# power_dist.net
KiCad netlist of a schematic drawn in EAGLE
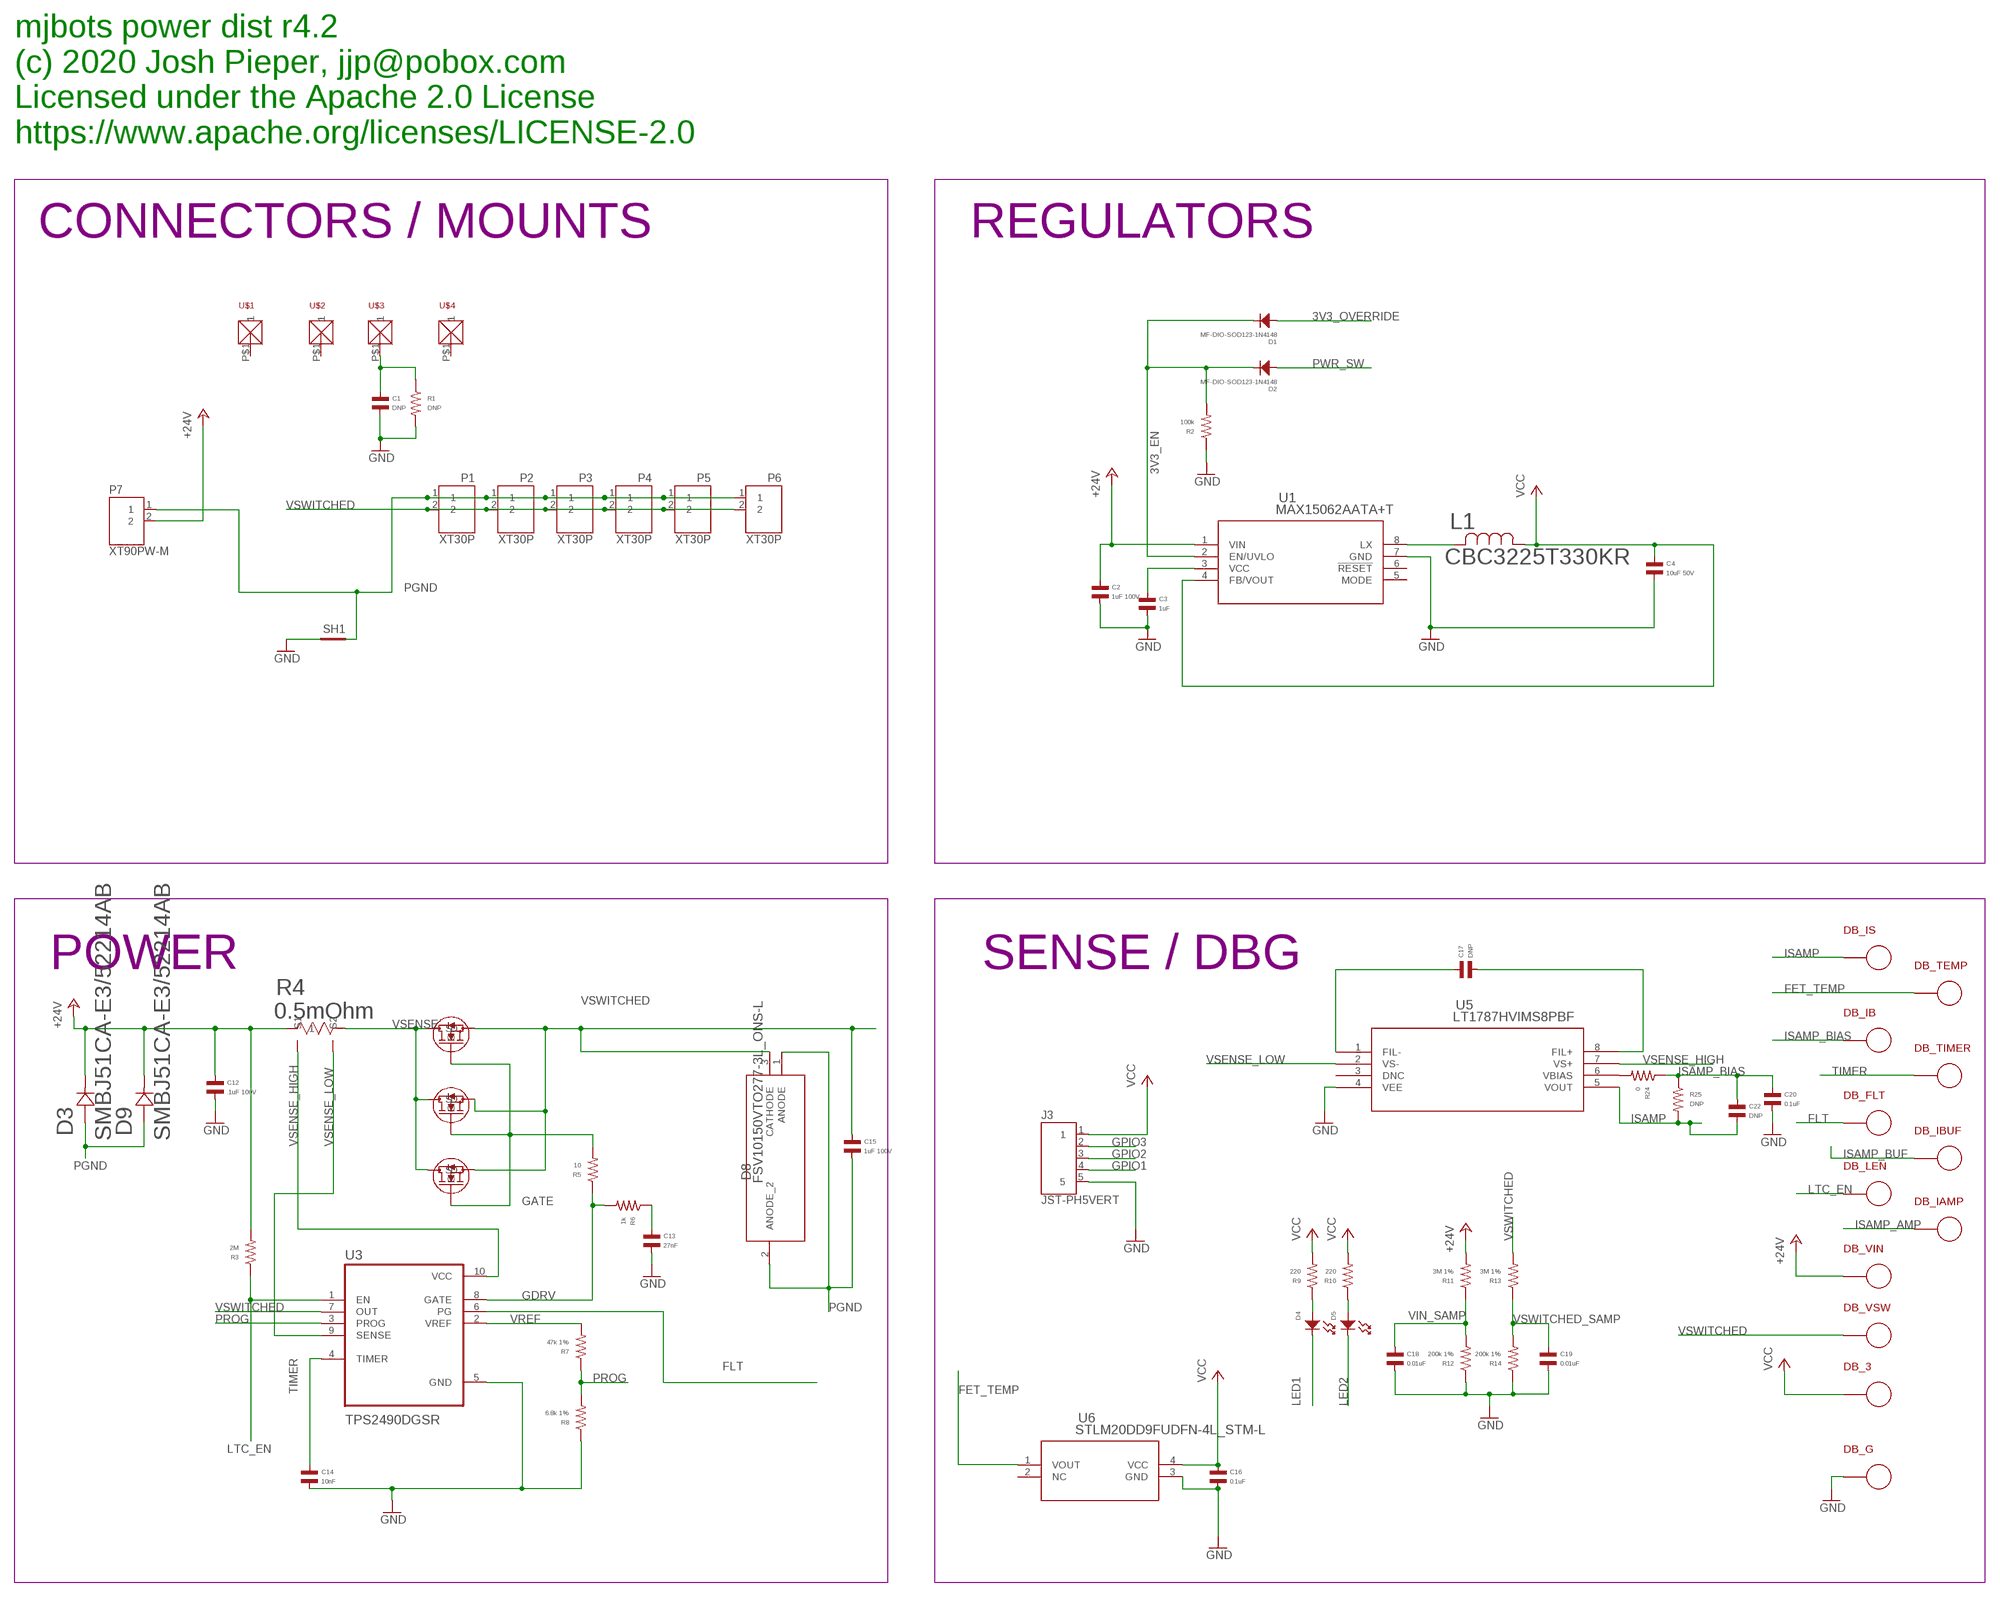
[diagram p0: schematic, sheet 1, part 1 of 2]
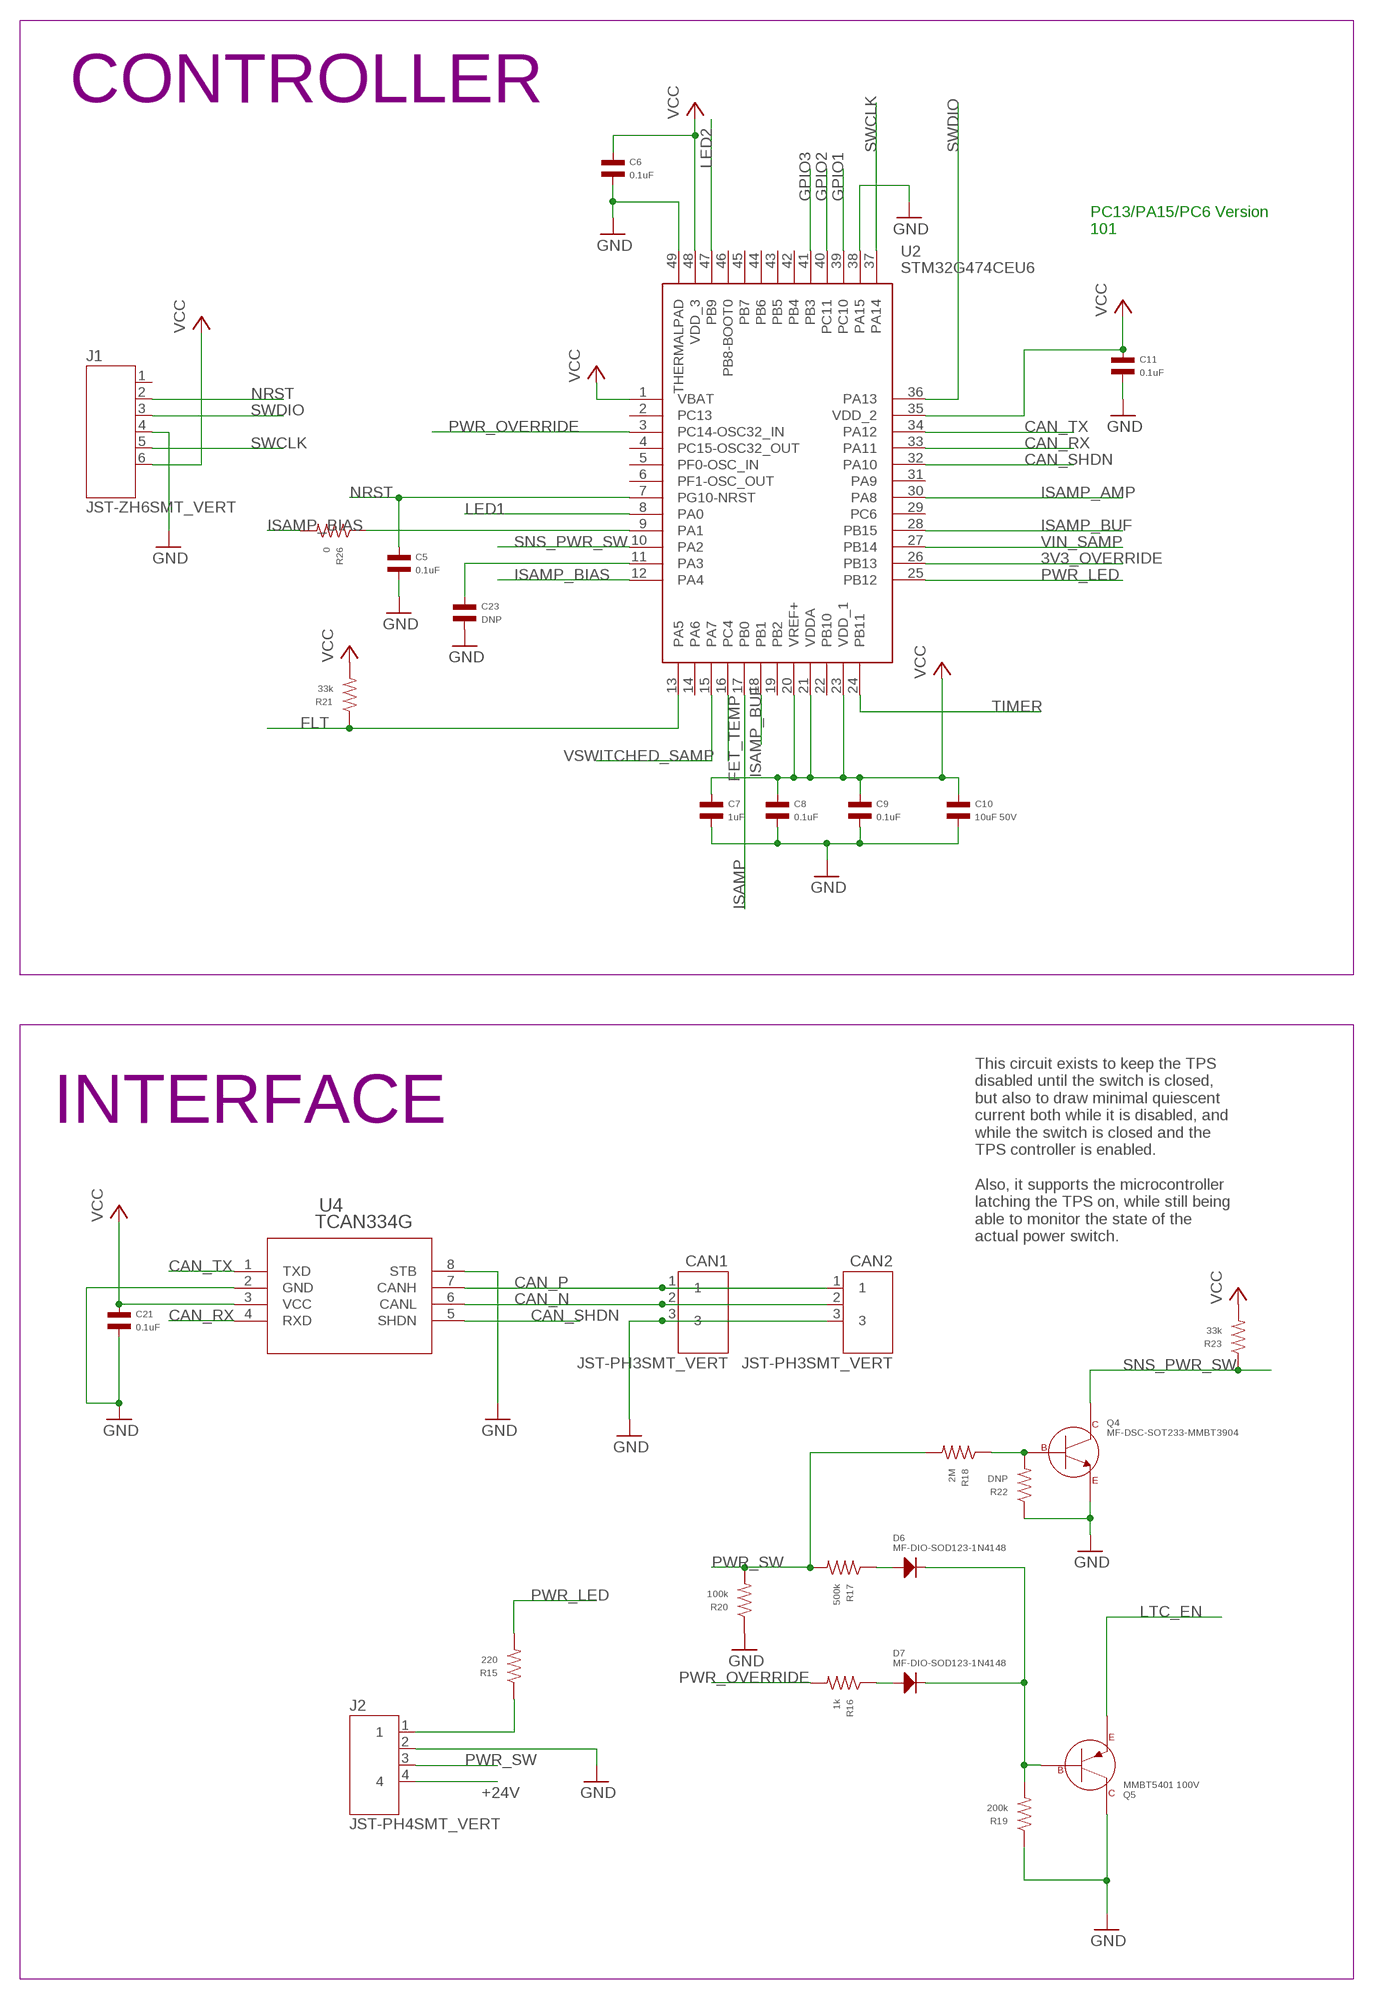
[diagram p1: schematic, sheet 1, part 2 of 2]

(export (version "E")
  (design (tool "Eeschema 10.0.6"))
  (components
    (comp (ref "C1")
      (value "DNP")
      (footprint "eagle-import:C0603")
      (fields (field (name "POPULATE") "0"))
      (libsource (lib "eagle-import") (part "CAPACITOR_NP_0603"))
    )
    (comp (ref "C2")
      (value "1uF 100V")
      (footprint "eagle-import:C0805")
      (fields (field (name "MF") "MURATA") (field (name "MPN") "GCM21BC72A105KE36L"))
      (libsource (lib "eagle-import") (part "CAPACITOR_NP_0805"))
    )
    (comp (ref "C3")
      (value "1uF")
      (footprint "eagle-import:C0603")
      (fields (field (name "HOUSEPART") "1") (field (name "MPN") "MF-CAP-0603-1uF"))
      (libsource (lib "eagle-import") (part "CAPACITOR_NP_0603"))
    )
    (comp (ref "C4")
      (value "10uF 50V")
      (footprint "eagle-import:C1206")
      (fields (field (name "MF") "TDK") (field (name "MPN") "C3216X7R1H106K160AE"))
      (libsource (lib "eagle-import") (part "CAPACITOR_NP_1206"))
    )
    (comp (ref "C5")
      (value "0.1uF")
      (footprint "eagle-import:C0603")
      (fields (field (name "HOUSEPART") "1") (field (name "MPN") "MF-CAP-0603-0.1uF"))
      (libsource (lib "eagle-import") (part "CAPACITOR_NP_0603"))
    )
    (comp (ref "C6")
      (value "0.1uF")
      (footprint "eagle-import:C0603")
      (fields (field (name "HOUSEPART") "1") (field (name "MPN") "MF-CAP-0603-0.1uF"))
      (libsource (lib "eagle-import") (part "CAPACITOR_NP_0603"))
    )
    (comp (ref "C7")
      (value "1uF")
      (footprint "eagle-import:C0603")
      (fields (field (name "HOUSEPART") "1") (field (name "MPN") "MF-CAP-0603-1uF"))
      (libsource (lib "eagle-import") (part "CAPACITOR_NP_0603"))
    )
    (comp (ref "C8")
      (value "0.1uF")
      (footprint "eagle-import:C0603")
      (fields (field (name "HOUSEPART") "1") (field (name "MPN") "MF-CAP-0603-0.1uF"))
      (libsource (lib "eagle-import") (part "CAPACITOR_NP_0603"))
    )
    (comp (ref "C9")
      (value "0.1uF")
      (footprint "eagle-import:C0603")
      (fields (field (name "HOUSEPART") "1") (field (name "MPN") "MF-CAP-0603-0.1uF"))
      (libsource (lib "eagle-import") (part "CAPACITOR_NP_0603"))
    )
    (comp (ref "C10")
      (value "10uF 50V")
      (footprint "eagle-import:C1206")
      (fields (field (name "MF") "TDK") (field (name "MPN") "C3216X7R1H106K160AE"))
      (libsource (lib "eagle-import") (part "CAPACITOR_NP_1206"))
    )
    (comp (ref "C11")
      (value "0.1uF")
      (footprint "eagle-import:C0603")
      (fields (field (name "HOUSEPART") "1") (field (name "MPN") "MF-CAP-0603-0.1uF"))
      (libsource (lib "eagle-import") (part "CAPACITOR_NP_0603"))
    )
    (comp (ref "C12")
      (value ".1uF 100V")
      (footprint "eagle-import:C0603")
      (fields (field (name "HOUSEPART") "1") (field (name "MPN") "MF-CAP-0603-0.1uF"))
      (libsource (lib "eagle-import") (part "CAPACITOR_NP_0603"))
    )
    (comp (ref "C13")
      (value "27nF")
      (footprint "eagle-import:C0603")
      (fields (field (name "HOUSEPART") "1"))
      (libsource (lib "eagle-import") (part "CAPACITOR_NP_0603"))
    )
    (comp (ref "C14")
      (value "10nF")
      (footprint "eagle-import:C0603")
      (fields (field (name "HOUSEPART") "1") (field (name "MPN") "MF-CAP-0603-0.1uF"))
      (libsource (lib "eagle-import") (part "CAPACITOR_NP_0603"))
    )
    (comp (ref "C15")
      (value "1uF 100V")
      (footprint "eagle-import:C0805")
      (fields (field (name "MF") "MURATA") (field (name "MPN") "GCM21BC72A105KE36L"))
      (libsource (lib "eagle-import") (part "CAPACITOR_NP_0805"))
    )
    (comp (ref "C16")
      (value "0.1uF")
      (footprint "eagle-import:C0603")
      (fields (field (name "HOUSEPART") "1") (field (name "MPN") "MF-CAP-0603-0.1uF"))
      (libsource (lib "eagle-import") (part "CAPACITOR_NP_0603"))
    )
    (comp (ref "C17")
      (value "DNP")
      (footprint "eagle-import:C0603")
      (fields (field (name "POPULATE") "0"))
      (libsource (lib "eagle-import") (part "CAPACITOR_NP_0603"))
    )
    (comp (ref "C18")
      (value "0.01uF")
      (footprint "eagle-import:C0603")
      (fields (field (name "HOUSEPART") "1") (field (name "MPN") "MF-CAP-0603-0.01uF"))
      (libsource (lib "eagle-import") (part "CAPACITOR_NP_0603"))
    )
    (comp (ref "C19")
      (value "0.01uF")
      (footprint "eagle-import:C0603")
      (fields (field (name "HOUSEPART") "1") (field (name "MPN") "MF-CAP-0603-0.01uF"))
      (libsource (lib "eagle-import") (part "CAPACITOR_NP_0603"))
    )
    (comp (ref "C20")
      (value "0.1uF")
      (footprint "eagle-import:C0603")
      (fields (field (name "HOUSEPART") "1") (field (name "MPN") "MF-CAP-0603-0.1uF"))
      (libsource (lib "eagle-import") (part "CAPACITOR_NP_0603"))
    )
    (comp (ref "C21")
      (value "0.1uF")
      (footprint "eagle-import:C0603")
      (fields (field (name "HOUSEPART") "1") (field (name "MPN") "MF-CAP-0603-0.1uF"))
      (libsource (lib "eagle-import") (part "CAPACITOR_NP_0603"))
    )
    (comp (ref "C22")
      (value "DNP")
      (footprint "eagle-import:C0603")
      (fields (field (name "HOUSEPART") "1") (field (name "POPULATE") "0"))
      (libsource (lib "eagle-import") (part "CAPACITOR_NP_0603"))
    )
    (comp (ref "C23")
      (value "DNP")
      (footprint "eagle-import:C0603")
      (fields (field (name "HOUSEPART") "1") (field (name "POPULATE") "0"))
      (libsource (lib "eagle-import") (part "CAPACITOR_NP_0603"))
    )
    (comp (ref "CAN1")
      (value "JST-PH3SMT_VERT")
      (footprint "eagle-import:JST_B3B_PH-SM4-TB(LF)(SN)")
      (fields (field (name "MF") "JST") (field (name "MPN") "B3B-PH-SM4-TB(LF)(SN)"))
      (libsource (lib "eagle-import") (part "JST-PH3SMT_VERT"))
    )
    (comp (ref "CAN2")
      (value "JST-PH3SMT_VERT")
      (footprint "eagle-import:JST_B3B_PH-SM4-TB(LF)(SN)")
      (fields (field (name "MF") "JST") (field (name "MPN") "B3B-PH-SM4-TB(LF)(SN)"))
      (libsource (lib "eagle-import") (part "JST-PH3SMT_VERT"))
    )
    (comp (ref "D1")
      (value "MF-DIO-SOD123-1N4148")
      (footprint "eagle-import:SOD-123")
      (fields (field (name "HOUSEPART") "YES"))
      (libsource (lib "eagle-import") (part "DIODES_SOD-123_1N4148"))
    )
    (comp (ref "D2")
      (value "MF-DIO-SOD123-1N4148")
      (footprint "eagle-import:SOD-123")
      (fields (field (name "HOUSEPART") "YES"))
      (libsource (lib "eagle-import") (part "DIODES_SOD-123_1N4148"))
    )
    (comp (ref "D3")
      (value "SMBJ51CA-E3/52214AB")
      (footprint "eagle-import:DIODE_DO-214AB")
      (fields (field (name "MPN") "SMC5K51A-M3/I"))
      (libsource (lib "eagle-import") (part "SMBJ51CA-E3/52214AB"))
    )
    (comp (ref "D4")
      (value "LED_SINGLE-0603")
      (footprint "eagle-import:LED0603")
      (fields
        (field (name "HOUSEPART") "NO")
        (field (name "HOUSEPART_1") "1")
        (field (name "MPN") "MF-LED-0603-RED")
      )
      (libsource (lib "eagle-import") (part "LED_SINGLE-0603"))
    )
    (comp (ref "D5")
      (value "LED_SINGLE-0603")
      (footprint "eagle-import:LED0603")
      (fields
        (field (name "HOUSEPART") "NO")
        (field (name "HOUSEPART_1") "1")
        (field (name "MPN") "MF-LED-0603-RED")
      )
      (libsource (lib "eagle-import") (part "LED_SINGLE-0603"))
    )
    (comp (ref "D6")
      (value "MF-DIO-SOD123-1N4148")
      (footprint "eagle-import:SOD-123")
      (fields (field (name "HOUSEPART") "YES"))
      (libsource (lib "eagle-import") (part "DIODES_SOD-123_1N4148"))
    )
    (comp (ref "D7")
      (value "MF-DIO-SOD123-1N4148")
      (footprint "eagle-import:SOD-123")
      (fields (field (name "HOUSEPART") "YES"))
      (libsource (lib "eagle-import") (part "DIODES_SOD-123_1N4148"))
    )
    (comp (ref "D8")
      (value "FSV10150VTO277-3L_ONS-L")
      (footprint "eagle-import:TO277-3L_ONS-L")
      (fields
        (field (name "MANUFACTURER_PART_NUMBER") "FSV10150V")
        (field (name "COPYRIGHT") "Copyright (C) 2018 Accelerated Designs. All rights reserved")
      )
      (libsource (lib "eagle-import") (part "FSV10150VTO277-3L_ONS-L"))
    )
    (comp (ref "D9")
      (value "SMBJ51CA-E3/52214AB")
      (footprint "eagle-import:DIODE_DO-214AB")
      (fields (field (name "MPN") "SMC5K51A-M3/I"))
      (libsource (lib "eagle-import") (part "SMBJ51CA-E3/52214AB"))
    )
    (comp (ref "DB_3")
      (value "PAD24AWG_PAD")
      (footprint "eagle-import:24AWG_PAD")
      (libsource (lib "eagle-import") (part "PAD24AWG_PAD"))
    )
    (comp (ref "DB_FLT")
      (value "PAD24AWG_PAD")
      (footprint "eagle-import:24AWG_PAD")
      (libsource (lib "eagle-import") (part "PAD24AWG_PAD"))
    )
    (comp (ref "DB_G")
      (value "PAD24AWG_PAD")
      (footprint "eagle-import:24AWG_PAD")
      (libsource (lib "eagle-import") (part "PAD24AWG_PAD"))
    )
    (comp (ref "DB_IAMP")
      (value "PAD24AWG_PAD")
      (footprint "eagle-import:24AWG_PAD")
      (libsource (lib "eagle-import") (part "PAD24AWG_PAD"))
    )
    (comp (ref "DB_IB")
      (value "PAD24AWG_PAD")
      (footprint "eagle-import:24AWG_PAD")
      (libsource (lib "eagle-import") (part "PAD24AWG_PAD"))
    )
    (comp (ref "DB_IBUF")
      (value "PAD24AWG_PAD")
      (footprint "eagle-import:24AWG_PAD")
      (libsource (lib "eagle-import") (part "PAD24AWG_PAD"))
    )
    (comp (ref "DB_IS")
      (value "PAD24AWG_PAD")
      (footprint "eagle-import:24AWG_PAD")
      (libsource (lib "eagle-import") (part "PAD24AWG_PAD"))
    )
    (comp (ref "DB_LEN")
      (value "PAD24AWG_PAD")
      (footprint "eagle-import:24AWG_PAD")
      (libsource (lib "eagle-import") (part "PAD24AWG_PAD"))
    )
    (comp (ref "DB_TEMP")
      (value "PAD24AWG_PAD")
      (footprint "eagle-import:24AWG_PAD")
      (libsource (lib "eagle-import") (part "PAD24AWG_PAD"))
    )
    (comp (ref "DB_TIMER")
      (value "PAD24AWG_PAD")
      (footprint "eagle-import:24AWG_PAD")
      (libsource (lib "eagle-import") (part "PAD24AWG_PAD"))
    )
    (comp (ref "DB_VIN")
      (value "PAD24AWG_PAD")
      (footprint "eagle-import:24AWG_PAD")
      (libsource (lib "eagle-import") (part "PAD24AWG_PAD"))
    )
    (comp (ref "DB_VSW")
      (value "PAD24AWG_PAD")
      (footprint "eagle-import:24AWG_PAD")
      (libsource (lib "eagle-import") (part "PAD24AWG_PAD"))
    )
    (comp (ref "J1")
      (value "JST-ZH6SMT_VERT")
      (footprint "eagle-import:JST_B6B-ZR-SM4-TF(LF)(SN)")
      (fields (field (name "MF") "JST") (field (name "MPN") "B6B-ZR-SM4-TF(LF)(SN)"))
      (libsource (lib "eagle-import") (part "JST-ZH6SMT_VERT"))
    )
    (comp (ref "J2")
      (value "JST-PH4SMT_VERT")
      (footprint "eagle-import:JST_B4B_PH-SM4-TB(LF)(SN)")
      (fields (field (name "MF") "JST") (field (name "MPN") "B4B-PH-SM4-TB(LF)(SN)"))
      (libsource (lib "eagle-import") (part "JST-PH4SMT_VERT"))
    )
    (comp (ref "J3")
      (value "JST-PH5VERT")
      (footprint "eagle-import:JST_B5B_PH-SM4-TB(LF)(SN)")
      (fields (field (name "MF") "JST") (field (name "MPN") "B5B-PH-SM4-TB(LF)(SN)"))
      (libsource (lib "eagle-import") (part "JST-PH5VERT"))
    )
    (comp (ref "L1")
      (value "CBC3225T330KR")
      (footprint "eagle-import:IND_TAIYO_CBC3225_TAY")
      (libsource (lib "eagle-import") (part "CBC3225T330KR"))
    )
    (comp (ref "P1")
      (value "XT30P")
      (footprint "eagle-import:XT30P")
      (fields (field (name "MF") "AMASS") (field (name "MPN") "XT30UPB-F"))
      (libsource (lib "eagle-import") (part "XT30P"))
    )
    (comp (ref "P2")
      (value "XT30P")
      (footprint "eagle-import:XT30P")
      (fields (field (name "MF") "AMASS") (field (name "MPN") "XT30UPB-F"))
      (libsource (lib "eagle-import") (part "XT30P"))
    )
    (comp (ref "P3")
      (value "XT30P")
      (footprint "eagle-import:XT30P")
      (fields (field (name "MF") "AMASS") (field (name "MPN") "XT30UPB-F"))
      (libsource (lib "eagle-import") (part "XT30P"))
    )
    (comp (ref "P4")
      (value "XT30P")
      (footprint "eagle-import:XT30P")
      (fields (field (name "MF") "AMASS") (field (name "MPN") "XT30UPB-F"))
      (libsource (lib "eagle-import") (part "XT30P"))
    )
    (comp (ref "P5")
      (value "XT30P")
      (footprint "eagle-import:XT30P")
      (fields (field (name "MF") "AMASS") (field (name "MPN") "XT30UPB-F"))
      (libsource (lib "eagle-import") (part "XT30P"))
    )
    (comp (ref "P6")
      (value "XT30P")
      (footprint "eagle-import:XT30P")
      (fields (field (name "MF") "AMASS") (field (name "MPN") "XT30UPB-F"))
      (libsource (lib "eagle-import") (part "XT30P"))
    )
    (comp (ref "P7")
      (value "XT90PW-M")
      (footprint "eagle-import:XT90PW-M")
      (libsource (lib "eagle-import") (part "XT90PW-M"))
    )
    (comp (ref "Q1")
      (value "PSMN4R8-100BSEJ")
      (footprint "eagle-import:D2PAK_SOT404_NEX")
      (fields
        (field (name "MANUFACTURER_PART_NUMBER") "PSMN3R7-100BSE")
        (field (name "MPN") "PSMN3R7-100BSE")
        (field (name "COPYRIGHT") "Copyright (C) 2018 Accelerated Designs. All rights reserved")
      )
      (libsource (lib "eagle-import") (part "PSMN4R8-100BSEJ"))
    )
    (comp (ref "Q2")
      (value "PSMN4R8-100BSEJ")
      (footprint "eagle-import:D2PAK_SOT404_NEX")
      (fields
        (field (name "MANUFACTURER_PART_NUMBER") "PSMN3R7-100BSE")
        (field (name "MPN") "PSMN3R7-100BSE")
        (field (name "COPYRIGHT") "Copyright (C) 2018 Accelerated Designs. All rights reserved")
      )
      (libsource (lib "eagle-import") (part "PSMN4R8-100BSEJ"))
    )
    (comp (ref "Q3")
      (value "PSMN4R8-100BSEJ")
      (footprint "eagle-import:D2PAK_SOT404_NEX")
      (fields
        (field (name "MANUFACTURER_PART_NUMBER") "PSMN3R7-100BSE")
        (field (name "MPN") "PSMN3R7-100BSE")
        (field (name "COPYRIGHT") "Copyright (C) 2018 Accelerated Designs. All rights reserved")
      )
      (libsource (lib "eagle-import") (part "PSMN4R8-100BSEJ"))
    )
    (comp (ref "Q4")
      (value "MF-DSC-SOT233-MMBT3904")
      (footprint "eagle-import:SOT-23-3")
      (fields (field (name "HOUSEPART") "YES"))
      (libsource (lib "eagle-import") (part "NPN_BJT_SOT-23-3MMBT3904"))
    )
    (comp (ref "Q5")
      (value "MMBT5401 100V")
      (footprint "eagle-import:SOT-23-3")
      (fields
        (field (name "HOUSEPART") "YES")
        (field (name "MPN") "MF-DSC-SOT233-MMBT3906")
        (field (name "MF") "DIODES")
        (field (name "MPN_1") "MMBT5401-7-F")
      )
      (libsource (lib "eagle-import") (part "PNP_BJT_SOT-23-3_MMBT3906"))
    )
    (comp (ref "R1")
      (value "DNP")
      (footprint "eagle-import:R0603")
      (fields (field (name "POPULATE") "0"))
      (libsource (lib "eagle-import") (part "RESISTOR_0603"))
    )
    (comp (ref "R2")
      (value "100k")
      (footprint "eagle-import:R0603")
      (fields (field (name "HOUSEPART") "1"))
      (libsource (lib "eagle-import") (part "RESISTOR_0603"))
    )
    (comp (ref "R3")
      (value "2M")
      (footprint "eagle-import:R0603")
      (fields (field (name "HOUSEPART") "1"))
      (libsource (lib "eagle-import") (part "RESISTOR_0603"))
    )
    (comp (ref "R4")
      (value "0.5mOhm")
      (footprint "eagle-import:SHUNT2512")
      (fields (field (name "MF") "VISHAY DALE") (field (name "MPN") "WSLF2512L5000FEA"))
      (libsource (lib "eagle-import") (part "SENSE_RESISTOR2512"))
    )
    (comp (ref "R5")
      (value "10")
      (footprint "eagle-import:R0603")
      (fields (field (name "HOUSEPART") "1"))
      (libsource (lib "eagle-import") (part "RESISTOR_0603"))
    )
    (comp (ref "R6")
      (value "1k")
      (footprint "eagle-import:R0603")
      (fields (field (name "HOUSEPART") "1"))
      (libsource (lib "eagle-import") (part "RESISTOR_0603"))
    )
    (comp (ref "R7")
      (value "47k 1%")
      (footprint "eagle-import:R0603")
      (fields (field (name "HOUSEPART") "1"))
      (libsource (lib "eagle-import") (part "RESISTOR_0603"))
    )
    (comp (ref "R8")
      (value "6.8k 1%")
      (footprint "eagle-import:R0603")
      (fields (field (name "HOUSEPART") "1"))
      (libsource (lib "eagle-import") (part "RESISTOR_0603"))
    )
    (comp (ref "R9")
      (value "220")
      (footprint "eagle-import:R0603")
      (fields (field (name "HOUSEPART") "1") (field (name "MPN") "MF-RES-0603-220"))
      (libsource (lib "eagle-import") (part "RESISTOR_0603"))
    )
    (comp (ref "R10")
      (value "220")
      (footprint "eagle-import:R0603")
      (fields (field (name "HOUSEPART") "1") (field (name "MPN") "MF-RES-0603-220"))
      (libsource (lib "eagle-import") (part "RESISTOR_0603"))
    )
    (comp (ref "R11")
      (value "3M 1%")
      (footprint "eagle-import:R0603")
      (fields (field (name "HOUSEPART") "1"))
      (libsource (lib "eagle-import") (part "RESISTOR_0603"))
    )
    (comp (ref "R12")
      (value "200k 1%")
      (footprint "eagle-import:R0603")
      (fields (field (name "HOUSEPART") "1"))
      (libsource (lib "eagle-import") (part "RESISTOR_0603"))
    )
    (comp (ref "R13")
      (value "3M 1%")
      (footprint "eagle-import:R0603")
      (fields (field (name "HOUSEPART") "1"))
      (libsource (lib "eagle-import") (part "RESISTOR_0603"))
    )
    (comp (ref "R14")
      (value "200k 1%")
      (footprint "eagle-import:R0603")
      (fields (field (name "HOUSEPART") "1"))
      (libsource (lib "eagle-import") (part "RESISTOR_0603"))
    )
    (comp (ref "R15")
      (value "220")
      (footprint "eagle-import:R0603")
      (fields (field (name "HOUSEPART") "1") (field (name "MPN") "MF-RES-0603-220"))
      (libsource (lib "eagle-import") (part "RESISTOR_0603"))
    )
    (comp (ref "R16")
      (value "1k")
      (footprint "eagle-import:R0603")
      (fields (field (name "HOUSEPART") "1"))
      (libsource (lib "eagle-import") (part "RESISTOR_0603"))
    )
    (comp (ref "R17")
      (value "500k")
      (footprint "eagle-import:R0603")
      (fields (field (name "HOUSEPART") "1"))
      (libsource (lib "eagle-import") (part "RESISTOR_0603"))
    )
    (comp (ref "R18")
      (value "2M")
      (footprint "eagle-import:R0603")
      (fields (field (name "HOUSEPART") "1"))
      (libsource (lib "eagle-import") (part "RESISTOR_0603"))
    )
    (comp (ref "R19")
      (value "200k")
      (footprint "eagle-import:R0603")
      (fields (field (name "HOUSEPART") "1"))
      (libsource (lib "eagle-import") (part "RESISTOR_0603"))
    )
    (comp (ref "R20")
      (value "100k")
      (footprint "eagle-import:R0603")
      (fields (field (name "HOUSEPART") "1"))
      (libsource (lib "eagle-import") (part "RESISTOR_0603"))
    )
    (comp (ref "R21")
      (value "33k")
      (footprint "eagle-import:R0603")
      (fields (field (name "HOUSEPART") "1"))
      (libsource (lib "eagle-import") (part "RESISTOR_0603"))
    )
    (comp (ref "R22")
      (value "DNP")
      (footprint "eagle-import:R0603")
      (fields (field (name "HOUSEPART") "1"))
      (libsource (lib "eagle-import") (part "RESISTOR_0603"))
    )
    (comp (ref "R23")
      (value "33k")
      (footprint "eagle-import:R0603")
      (fields (field (name "HOUSEPART") "1"))
      (libsource (lib "eagle-import") (part "RESISTOR_0603"))
    )
    (comp (ref "R24")
      (value "0")
      (footprint "eagle-import:R0603")
      (fields (field (name "HOUSEPART") "1"))
      (libsource (lib "eagle-import") (part "RESISTOR_0603"))
    )
    (comp (ref "R25")
      (value "DNP")
      (footprint "eagle-import:R0603")
      (fields (field (name "HOUSEPART") "1"))
      (libsource (lib "eagle-import") (part "RESISTOR_0603"))
    )
    (comp (ref "R26")
      (value "0")
      (footprint "eagle-import:R0603")
      (fields (field (name "HOUSEPART") "1"))
      (libsource (lib "eagle-import") (part "RESISTOR_0603"))
    )
    (comp (ref "SH1")
      (value "SHORTBIG")
      (footprint "eagle-import:SHORT_TOP-BIG")
      (libsource (lib "eagle-import") (part "SHORTBIG"))
    )
    (comp (ref "U$1")
      (value "MOUNT")
      (footprint "eagle-import:M2.5MOUNT")
      (libsource (lib "eagle-import") (part "MOUNT"))
    )
    (comp (ref "U$2")
      (value "MOUNT")
      (footprint "eagle-import:M2.5MOUNT")
      (libsource (lib "eagle-import") (part "MOUNT"))
    )
    (comp (ref "U$3")
      (value "MOUNT")
      (footprint "eagle-import:M2.5MOUNT")
      (libsource (lib "eagle-import") (part "MOUNT"))
    )
    (comp (ref "U$4")
      (value "MOUNT")
      (footprint "eagle-import:M2.5MOUNT")
      (libsource (lib "eagle-import") (part "MOUNT"))
    )
    (comp (ref "U1")
      (value "MAX15062AATA+T")
      (footprint "eagle-import:21-0487A_MXM")
      (fields (field (name "COPYRIGHT") "Copyright (C) 2018 Accelerated Designs. All rights reserved"))
      (libsource (lib "eagle-import") (part "MAX15062AATA+T"))
    )
    (comp (ref "U2")
      (value "STM32G474CEU6")
      (footprint "eagle-import:QFN50P700X700X60-49N")
      (fields (field (name "MOUSER_PART_NUMBER") "511-STM32G474CEU6") (field (name "MF") "ST"))
      (libsource (lib "eagle-import") (part "STM32G474CEU6"))
    )
    (comp (ref "U3")
      (value "TPS2490DGSR")
      (footprint "eagle-import:SOP50P490X110-10N")
      (fields (field (name "DIGI-KEY_PART_NUMBER") "296-26924-1-ND") (field (name "MF") "Texas Instruments"))
      (libsource (lib "eagle-import") (part "TPS2490DGSR"))
    )
    (comp (ref "U4")
      (value "TCAN334G")
      (footprint "eagle-import:SOIC8")
      (fields (field (name "MF") "TI") (field (name "MPN") "TCAN334GDR"))
      (libsource (lib "eagle-import") (part "TCAN334G"))
    )
    (comp (ref "U5")
      (value "LT1787HVIMS8PBF")
      (footprint "eagle-import:MSOP-8_MS")
      (fields
        (field (name "DIGI-KEY_PART_NUMBER") "LT1787HVIMS8#PBF-ND")
        (field (name "MF") "Linear Technology")
        (field (name "MP") "LT1787HVIMS8#PBF")
      )
      (libsource (lib "eagle-import") (part "LT1787HVIMS8PBF"))
    )
    (comp (ref "U6")
      (value "STLM20DD9FUDFN-4L_STM-L")
      (footprint "eagle-import:UDFN-4L_STM-L")
      (fields
        (field (name "MANUFACTURER_PART_NUMBER") "STLM20DD9F")
        (field (name "COPYRIGHT") "Copyright (C) 2018 Accelerated Designs. All rights reserved")
      )
      (libsource (lib "eagle-import") (part "STLM20DD9FUDFN-4L_STM-L"))
    )
  )
  (nets
    (net (code "1") (name "+24V") (class "Default")
      (node (ref "C12") (pin "P$1") (pinfunction "P$1_P$1") (pintype "passive"))
      (node (ref "C2") (pin "P$1") (pinfunction "P$1_P$1") (pintype "passive"))
      (node (ref "D3") (pin "P$1") (pinfunction "1_P$1") (pintype "passive"))
      (node (ref "D9") (pin "P$1") (pinfunction "1_P$1") (pintype "passive"))
      (node (ref "DB_VIN") (pin "P$1") (pinfunction "P$1_P$1") (pintype "bidirectional"))
      (node (ref "J2") (pin "4") (pinfunction "4_4") (pintype "passive"))
      (node (ref "P7") (pin "2") (pinfunction "2_2") (pintype "passive"))
      (node (ref "R11") (pin "P$2") (pinfunction "P$2_P$2") (pintype "passive"))
      (node (ref "R3") (pin "P$2") (pinfunction "P$2_P$2") (pintype "passive"))
      (node (ref "R4") (pin "1") (pinfunction "1_1") (pintype "passive"))
      (node (ref "U1") (pin "1") (pinfunction "VIN_1") (pintype "input"))
    )
    (net (code "2") (name "/3V3_EN") (class "Default")
      (node (ref "D1") (pin "CATHODE") (pinfunction "CATHODE_CATHODE") (pintype "bidirectional"))
      (node (ref "D2") (pin "CATHODE") (pinfunction "CATHODE_CATHODE") (pintype "bidirectional"))
      (node (ref "R2") (pin "P$2") (pinfunction "P$2_P$2") (pintype "passive"))
      (node (ref "U1") (pin "2") (pinfunction "EN/UVLO_2") (pintype "input"))
    )
    (net (code "3") (name "/3V3_OVERRIDE") (class "Default")
      (node (ref "D1") (pin "ANODE") (pinfunction "ANODE_ANODE") (pintype "bidirectional"))
      (node (ref "U2") (pin "26") (pinfunction "PB13_26") (pintype "bidirectional"))
    )
    (net (code "4") (name "/CAN_N") (class "Default")
      (node (ref "CAN1") (pin "2") (pinfunction "2_2") (pintype "passive"))
      (node (ref "CAN2") (pin "2") (pinfunction "2_2") (pintype "passive"))
      (node (ref "U4") (pin "6") (pinfunction "CANL_6") (pintype "bidirectional"))
    )
    (net (code "5") (name "/CAN_P") (class "Default")
      (node (ref "CAN1") (pin "1") (pinfunction "1_1") (pintype "passive"))
      (node (ref "CAN2") (pin "1") (pinfunction "1_1") (pintype "passive"))
      (node (ref "U4") (pin "7") (pinfunction "CANH_7") (pintype "bidirectional"))
    )
    (net (code "6") (name "/CAN_RX") (class "Default")
      (node (ref "U2") (pin "33") (pinfunction "PA11_33") (pintype "bidirectional"))
      (node (ref "U4") (pin "4") (pinfunction "RXD_4") (pintype "output"))
    )
    (net (code "7") (name "/CAN_SHDN") (class "Default")
      (node (ref "U2") (pin "32") (pinfunction "PA10_32") (pintype "bidirectional"))
      (node (ref "U4") (pin "5") (pinfunction "SHDN_5") (pintype "input"))
    )
    (net (code "8") (name "/CAN_TX") (class "Default")
      (node (ref "U2") (pin "34") (pinfunction "PA12_34") (pintype "bidirectional"))
      (node (ref "U4") (pin "1") (pinfunction "TXD_1") (pintype "input"))
    )
    (net (code "9") (name "/FET_TEMP") (class "Default")
      (node (ref "DB_TEMP") (pin "P$1") (pinfunction "P$1_P$1") (pintype "bidirectional"))
      (node (ref "U2") (pin "16") (pinfunction "PC4_16") (pintype "bidirectional"))
      (node (ref "U6") (pin "1") (pinfunction "VOUT_1") (pintype "output"))
    )
    (net (code "10") (name "/FLT") (class "Default")
      (node (ref "DB_FLT") (pin "P$1") (pinfunction "P$1_P$1") (pintype "bidirectional"))
      (node (ref "R21") (pin "P$1") (pinfunction "P$1_P$1") (pintype "passive"))
      (node (ref "U2") (pin "13") (pinfunction "PA5_13") (pintype "bidirectional"))
      (node (ref "U3") (pin "6") (pinfunction "PG_6") (pintype "output"))
    )
    (net (code "11") (name "/GATE") (class "Default")
      (node (ref "Q1") (pin "1") (pinfunction "G_1") (pintype "passive"))
      (node (ref "Q2") (pin "1") (pinfunction "G_1") (pintype "passive"))
      (node (ref "Q3") (pin "1") (pinfunction "G_1") (pintype "passive"))
      (node (ref "R5") (pin "P$2") (pinfunction "P$2_P$2") (pintype "passive"))
    )
    (net (code "12") (name "/GDRV") (class "Default")
      (node (ref "R5") (pin "P$1") (pinfunction "P$1_P$1") (pintype "passive"))
      (node (ref "R6") (pin "P$2") (pinfunction "P$2_P$2") (pintype "passive"))
      (node (ref "U3") (pin "8") (pinfunction "GATE_8") (pintype "output"))
    )
    (net (code "13") (name "/GPIO1") (class "Default")
      (node (ref "J3") (pin "4") (pinfunction "4_4") (pintype "passive"))
      (node (ref "U2") (pin "39") (pinfunction "PC10_39") (pintype "bidirectional"))
    )
    (net (code "14") (name "/GPIO2") (class "Default")
      (node (ref "J3") (pin "3") (pinfunction "3_3") (pintype "passive"))
      (node (ref "U2") (pin "40") (pinfunction "PC11_40") (pintype "bidirectional"))
    )
    (net (code "15") (name "/GPIO3") (class "Default")
      (node (ref "J3") (pin "2") (pinfunction "2_2") (pintype "passive"))
      (node (ref "U2") (pin "41") (pinfunction "PB3_41") (pintype "bidirectional"))
    )
    (net (code "16") (name "/ISAMP") (class "Default")
      (node (ref "C22") (pin "P$2") (pinfunction "P$2_P$2") (pintype "passive"))
      (node (ref "DB_IS") (pin "P$1") (pinfunction "P$1_P$1") (pintype "bidirectional"))
      (node (ref "R25") (pin "P$2") (pinfunction "P$2_P$2") (pintype "passive"))
      (node (ref "U2") (pin "17") (pinfunction "PB0_17") (pintype "bidirectional"))
      (node (ref "U5") (pin "5") (pinfunction "VOUT_5") (pintype "output"))
    )
    (net (code "17") (name "/ISAMP_AMP") (class "Default")
      (node (ref "DB_IAMP") (pin "P$1") (pinfunction "P$1_P$1") (pintype "bidirectional"))
      (node (ref "U2") (pin "30") (pinfunction "PA8_30") (pintype "bidirectional"))
    )
    (net (code "18") (name "/ISAMP_BIAS") (class "Default")
      (node (ref "C20") (pin "P$1") (pinfunction "P$1_P$1") (pintype "passive"))
      (node (ref "C22") (pin "P$1") (pinfunction "P$1_P$1") (pintype "passive"))
      (node (ref "DB_IB") (pin "P$1") (pinfunction "P$1_P$1") (pintype "bidirectional"))
      (node (ref "R24") (pin "P$1") (pinfunction "P$1_P$1") (pintype "passive"))
      (node (ref "R25") (pin "P$1") (pinfunction "P$1_P$1") (pintype "passive"))
      (node (ref "R26") (pin "P$2") (pinfunction "P$2_P$2") (pintype "passive"))
      (node (ref "U2") (pin "12") (pinfunction "PA4_12") (pintype "bidirectional"))
    )
    (net (code "19") (name "/ISAMP_BUF") (class "Default")
      (node (ref "DB_IBUF") (pin "P$1") (pinfunction "P$1_P$1") (pintype "bidirectional"))
      (node (ref "U2") (pin "18") (pinfunction "PB1_18") (pintype "bidirectional"))
      (node (ref "U2") (pin "28") (pinfunction "PB15_28") (pintype "bidirectional"))
    )
    (net (code "20") (name "/LED1") (class "Default")
      (node (ref "D4") (pin "CATHODE") (pinfunction "CATHODE_CATHODE") (pintype "power_in"))
      (node (ref "U2") (pin "8") (pinfunction "PA0_8") (pintype "bidirectional"))
    )
    (net (code "21") (name "/LED2") (class "Default")
      (node (ref "D5") (pin "CATHODE") (pinfunction "CATHODE_CATHODE") (pintype "power_in"))
      (node (ref "U2") (pin "47") (pinfunction "PB9_47") (pintype "bidirectional"))
    )
    (net (code "22") (name "/LTC_EN") (class "Default")
      (node (ref "DB_LEN") (pin "P$1") (pinfunction "P$1_P$1") (pintype "bidirectional"))
      (node (ref "Q5") (pin "P$2") (pinfunction "EMITTER_P$2") (pintype "bidirectional"))
      (node (ref "R3") (pin "P$1") (pinfunction "P$1_P$1") (pintype "passive"))
      (node (ref "U3") (pin "1") (pinfunction "EN_1") (pintype "input"))
    )
    (net (code "23") (name "/NRST") (class "Default")
      (node (ref "C5") (pin "P$1") (pinfunction "P$1_P$1") (pintype "passive"))
      (node (ref "J1") (pin "2") (pinfunction "2_2") (pintype "passive"))
      (node (ref "U2") (pin "7") (pinfunction "PG10-NRST_7") (pintype "bidirectional"))
    )
    (net (code "24") (name "/PGND") (class "Default")
      (node (ref "C15") (pin "P$2") (pinfunction "P$2_P$2") (pintype "passive"))
      (node (ref "D3") (pin "P$2") (pinfunction "2_P$2") (pintype "passive"))
      (node (ref "D8") (pin "1") (pinfunction "ANODE_1") (pintype "passive"))
      (node (ref "D8") (pin "2") (pinfunction "ANODE_2_2") (pintype "passive"))
      (node (ref "D9") (pin "P$2") (pinfunction "2_P$2") (pintype "passive"))
      (node (ref "P1") (pin "1") (pinfunction "1_1") (pintype "passive"))
      (node (ref "P2") (pin "1") (pinfunction "1_1") (pintype "passive"))
      (node (ref "P3") (pin "1") (pinfunction "1_1") (pintype "passive"))
      (node (ref "P4") (pin "1") (pinfunction "1_1") (pintype "passive"))
      (node (ref "P5") (pin "1") (pinfunction "1_1") (pintype "passive"))
      (node (ref "P6") (pin "1") (pinfunction "1_1") (pintype "passive"))
      (node (ref "P7") (pin "1") (pinfunction "1_1") (pintype "passive"))
      (node (ref "SH1") (pin "2") (pinfunction "P$2_2") (pintype "bidirectional"))
    )
    (net (code "25") (name "/PROG") (class "Default")
      (node (ref "R7") (pin "P$1") (pinfunction "P$1_P$1") (pintype "passive"))
      (node (ref "R8") (pin "P$2") (pinfunction "P$2_P$2") (pintype "passive"))
      (node (ref "U3") (pin "3") (pinfunction "PROG_3") (pintype "input"))
    )
    (net (code "26") (name "/PWR_LED") (class "Default")
      (node (ref "R15") (pin "P$2") (pinfunction "P$2_P$2") (pintype "passive"))
      (node (ref "U2") (pin "25") (pinfunction "PB12_25") (pintype "bidirectional"))
    )
    (net (code "27") (name "/PWR_OVERRIDE") (class "Default")
      (node (ref "R16") (pin "P$2") (pinfunction "P$2_P$2") (pintype "passive"))
      (node (ref "U2") (pin "3") (pinfunction "PC14-OSC32_IN_3") (pintype "bidirectional"))
    )
    (net (code "28") (name "/PWR_SW") (class "Default")
      (node (ref "D2") (pin "ANODE") (pinfunction "ANODE_ANODE") (pintype "bidirectional"))
      (node (ref "J2") (pin "3") (pinfunction "3_3") (pintype "passive"))
      (node (ref "R17") (pin "P$2") (pinfunction "P$2_P$2") (pintype "passive"))
      (node (ref "R18") (pin "P$2") (pinfunction "P$2_P$2") (pintype "passive"))
      (node (ref "R20") (pin "P$2") (pinfunction "P$2_P$2") (pintype "passive"))
    )
    (net (code "29") (name "/SNS_PWR_SW") (class "Default")
      (node (ref "Q4") (pin "P$3") (pinfunction "COLLECTOR_P$3") (pintype "bidirectional"))
      (node (ref "R23") (pin "P$1") (pinfunction "P$1_P$1") (pintype "passive"))
      (node (ref "U2") (pin "10") (pinfunction "PA2_10") (pintype "bidirectional"))
    )
    (net (code "30") (name "/SWCLK") (class "Default")
      (node (ref "J1") (pin "5") (pinfunction "5_5") (pintype "passive"))
      (node (ref "U2") (pin "37") (pinfunction "PA14_37") (pintype "bidirectional"))
    )
    (net (code "31") (name "/SWDIO") (class "Default")
      (node (ref "J1") (pin "3") (pinfunction "3_3") (pintype "passive"))
      (node (ref "U2") (pin "36") (pinfunction "PA13_36") (pintype "bidirectional"))
    )
    (net (code "32") (name "/TIMER") (class "Default")
      (node (ref "C14") (pin "P$1") (pinfunction "P$1_P$1") (pintype "passive"))
      (node (ref "DB_TIMER") (pin "P$1") (pinfunction "P$1_P$1") (pintype "bidirectional"))
      (node (ref "U2") (pin "24") (pinfunction "PB11_24") (pintype "bidirectional"))
      (node (ref "U3") (pin "4") (pinfunction "TIMER_4") (pintype "bidirectional"))
    )
    (net (code "33") (name "/VIN_SAMP") (class "Default")
      (node (ref "C18") (pin "P$1") (pinfunction "P$1_P$1") (pintype "passive"))
      (node (ref "R11") (pin "P$1") (pinfunction "P$1_P$1") (pintype "passive"))
      (node (ref "R12") (pin "P$2") (pinfunction "P$2_P$2") (pintype "passive"))
      (node (ref "U2") (pin "27") (pinfunction "PB14_27") (pintype "bidirectional"))
    )
    (net (code "34") (name "/VREF") (class "Default")
      (node (ref "R7") (pin "P$2") (pinfunction "P$2_P$2") (pintype "passive"))
      (node (ref "U3") (pin "2") (pinfunction "VREF_2") (pintype "output"))
    )
    (net (code "35") (name "/VSENSE") (class "Default")
      (node (ref "Q1") (pin "2") (pinfunction "D_2") (pintype "passive"))
      (node (ref "Q2") (pin "2") (pinfunction "D_2") (pintype "passive"))
      (node (ref "Q3") (pin "2") (pinfunction "D_2") (pintype "passive"))
      (node (ref "R4") (pin "2") (pinfunction "2_2") (pintype "passive"))
    )
    (net (code "36") (name "/VSENSE_HIGH") (class "Default")
      (node (ref "R4") (pin "3") (pinfunction "S1_3") (pintype "passive"))
      (node (ref "U3") (pin "10") (pinfunction "VCC_10") (pintype "power_in"))
      (node (ref "U5") (pin "7") (pinfunction "VS+_7") (pintype "input"))
    )
    (net (code "37") (name "/VSENSE_LOW") (class "Default")
      (node (ref "R4") (pin "4") (pinfunction "S2_4") (pintype "passive"))
      (node (ref "U3") (pin "9") (pinfunction "SENSE_9") (pintype "input"))
      (node (ref "U5") (pin "2") (pinfunction "VS-_2") (pintype "input"))
    )
    (net (code "38") (name "/VSWITCHED") (class "Default")
      (node (ref "C15") (pin "P$1") (pinfunction "P$1_P$1") (pintype "passive"))
      (node (ref "D8") (pin "3") (pinfunction "CATHODE_3") (pintype "passive"))
      (node (ref "DB_VSW") (pin "P$1") (pinfunction "P$1_P$1") (pintype "bidirectional"))
      (node (ref "P1") (pin "2") (pinfunction "2_2") (pintype "passive"))
      (node (ref "P2") (pin "2") (pinfunction "2_2") (pintype "passive"))
      (node (ref "P3") (pin "2") (pinfunction "2_2") (pintype "passive"))
      (node (ref "P4") (pin "2") (pinfunction "2_2") (pintype "passive"))
      (node (ref "P5") (pin "2") (pinfunction "2_2") (pintype "passive"))
      (node (ref "P6") (pin "2") (pinfunction "2_2") (pintype "passive"))
      (node (ref "Q1") (pin "3") (pinfunction "S_3") (pintype "passive"))
      (node (ref "Q2") (pin "3") (pinfunction "S_3") (pintype "passive"))
      (node (ref "Q3") (pin "3") (pinfunction "S_3") (pintype "passive"))
      (node (ref "R13") (pin "P$2") (pinfunction "P$2_P$2") (pintype "passive"))
      (node (ref "U3") (pin "7") (pinfunction "OUT_7") (pintype "input"))
    )
    (net (code "39") (name "/VSWITCHED_SAMP") (class "Default")
      (node (ref "C19") (pin "P$1") (pinfunction "P$1_P$1") (pintype "passive"))
      (node (ref "R13") (pin "P$1") (pinfunction "P$1_P$1") (pintype "passive"))
      (node (ref "R14") (pin "P$2") (pinfunction "P$2_P$2") (pintype "passive"))
      (node (ref "U2") (pin "15") (pinfunction "PA7_15") (pintype "bidirectional"))
    )
    (net (code "40") (name "GND") (class "Default")
      (node (ref "C1") (pin "P$2") (pinfunction "P$2_P$2") (pintype "passive"))
      (node (ref "C10") (pin "P$2") (pinfunction "P$2_P$2") (pintype "passive"))
      (node (ref "C11") (pin "P$2") (pinfunction "P$2_P$2") (pintype "passive"))
      (node (ref "C12") (pin "P$2") (pinfunction "P$2_P$2") (pintype "passive"))
      (node (ref "C13") (pin "P$2") (pinfunction "P$2_P$2") (pintype "passive"))
      (node (ref "C14") (pin "P$2") (pinfunction "P$2_P$2") (pintype "passive"))
      (node (ref "C16") (pin "P$2") (pinfunction "P$2_P$2") (pintype "passive"))
      (node (ref "C18") (pin "P$2") (pinfunction "P$2_P$2") (pintype "passive"))
      (node (ref "C19") (pin "P$2") (pinfunction "P$2_P$2") (pintype "passive"))
      (node (ref "C2") (pin "P$2") (pinfunction "P$2_P$2") (pintype "passive"))
      (node (ref "C20") (pin "P$2") (pinfunction "P$2_P$2") (pintype "passive"))
      (node (ref "C21") (pin "P$2") (pinfunction "P$2_P$2") (pintype "passive"))
      (node (ref "C23") (pin "P$2") (pinfunction "P$2_P$2") (pintype "passive"))
      (node (ref "C3") (pin "P$2") (pinfunction "P$2_P$2") (pintype "passive"))
      (node (ref "C4") (pin "P$2") (pinfunction "P$2_P$2") (pintype "passive"))
      (node (ref "C5") (pin "P$2") (pinfunction "P$2_P$2") (pintype "passive"))
      (node (ref "C6") (pin "P$2") (pinfunction "P$2_P$2") (pintype "passive"))
      (node (ref "C7") (pin "P$2") (pinfunction "P$2_P$2") (pintype "passive"))
      (node (ref "C8") (pin "P$2") (pinfunction "P$2_P$2") (pintype "passive"))
      (node (ref "C9") (pin "P$2") (pinfunction "P$2_P$2") (pintype "passive"))
      (node (ref "CAN1") (pin "3") (pinfunction "3_3") (pintype "passive"))
      (node (ref "CAN2") (pin "3") (pinfunction "3_3") (pintype "passive"))
      (node (ref "DB_G") (pin "P$1") (pinfunction "P$1_P$1") (pintype "bidirectional"))
      (node (ref "J1") (pin "4") (pinfunction "4_4") (pintype "passive"))
      (node (ref "J2") (pin "2") (pinfunction "2_2") (pintype "passive"))
      (node (ref "J3") (pin "5") (pinfunction "5_5") (pintype "passive"))
      (node (ref "Q4") (pin "P$2") (pinfunction "EMITTER_P$2") (pintype "bidirectional"))
      (node (ref "Q5") (pin "P$3") (pinfunction "COLLECTOR_P$3") (pintype "bidirectional"))
      (node (ref "R1") (pin "P$2") (pinfunction "P$2_P$2") (pintype "passive"))
      (node (ref "R12") (pin "P$1") (pinfunction "P$1_P$1") (pintype "passive"))
      (node (ref "R14") (pin "P$1") (pinfunction "P$1_P$1") (pintype "passive"))
      (node (ref "R19") (pin "P$1") (pinfunction "P$1_P$1") (pintype "passive"))
      (node (ref "R2") (pin "P$1") (pinfunction "P$1_P$1") (pintype "passive"))
      (node (ref "R20") (pin "P$1") (pinfunction "P$1_P$1") (pintype "passive"))
      (node (ref "R22") (pin "P$1") (pinfunction "P$1_P$1") (pintype "passive"))
      (node (ref "R8") (pin "P$1") (pinfunction "P$1_P$1") (pintype "passive"))
      (node (ref "SH1") (pin "1") (pinfunction "P$1_1") (pintype "bidirectional"))
      (node (ref "U1") (pin "7") (pinfunction "GND_7") (pintype "power_in"))
      (node (ref "U2") (pin "38") (pinfunction "PA15_38") (pintype "bidirectional"))
      (node (ref "U2") (pin "49") (pinfunction "THERMALPAD_49") (pintype "bidirectional"))
      (node (ref "U3") (pin "5") (pinfunction "GND_5") (pintype "power_in"))
      (node (ref "U4") (pin "2") (pinfunction "GND_2") (pintype "power_in"))
      (node (ref "U4") (pin "8") (pinfunction "STB_8") (pintype "input"))
      (node (ref "U5") (pin "4") (pinfunction "VEE_4") (pintype "power_in"))
      (node (ref "U6") (pin "3") (pinfunction "GND_3") (pintype "power_in"))
    )
    (net (code "41") (name "Net-(C13-PadP$1)") (class "Default")
      (node (ref "C13") (pin "P$1") (pinfunction "P$1_P$1") (pintype "passive"))
      (node (ref "R6") (pin "P$1") (pinfunction "P$1_P$1") (pintype "passive"))
    )
    (net (code "42") (name "Net-(D4-PadANODE)") (class "Default")
      (node (ref "D4") (pin "ANODE") (pinfunction "ANODE_ANODE") (pintype "power_in"))
      (node (ref "R9") (pin "P$1") (pinfunction "P$1_P$1") (pintype "passive"))
    )
    (net (code "43") (name "Net-(D5-PadANODE)") (class "Default")
      (node (ref "D5") (pin "ANODE") (pinfunction "ANODE_ANODE") (pintype "power_in"))
      (node (ref "R10") (pin "P$1") (pinfunction "P$1_P$1") (pintype "passive"))
    )
    (net (code "44") (name "Net-(D6-PadANODE)") (class "Default")
      (node (ref "D6") (pin "ANODE") (pinfunction "ANODE_ANODE") (pintype "bidirectional"))
      (node (ref "R17") (pin "P$1") (pinfunction "P$1_P$1") (pintype "passive"))
    )
    (net (code "45") (name "Net-(D7-PadANODE)") (class "Default")
      (node (ref "D7") (pin "ANODE") (pinfunction "ANODE_ANODE") (pintype "bidirectional"))
      (node (ref "R16") (pin "P$1") (pinfunction "P$1_P$1") (pintype "passive"))
    )
    (net (code "46") (name "Net-(J2-Pad1)") (class "Default")
      (node (ref "J2") (pin "1") (pinfunction "1_1") (pintype "passive"))
      (node (ref "R15") (pin "P$1") (pinfunction "P$1_P$1") (pintype "passive"))
    )
    (net (code "47") (name "Net-(Q4-BASE)") (class "Default")
      (node (ref "Q4") (pin "P$1") (pinfunction "BASE_P$1") (pintype "bidirectional"))
      (node (ref "R18") (pin "P$1") (pinfunction "P$1_P$1") (pintype "passive"))
      (node (ref "R22") (pin "P$2") (pinfunction "P$2_P$2") (pintype "passive"))
    )
    (net (code "48") (name "Net-(Q5-BASE)") (class "Default")
      (node (ref "D6") (pin "CATHODE") (pinfunction "CATHODE_CATHODE") (pintype "bidirectional"))
      (node (ref "D7") (pin "CATHODE") (pinfunction "CATHODE_CATHODE") (pintype "bidirectional"))
      (node (ref "Q5") (pin "P$1") (pinfunction "BASE_P$1") (pintype "bidirectional"))
      (node (ref "R19") (pin "P$2") (pinfunction "P$2_P$2") (pintype "passive"))
    )
    (net (code "49") (name "Net-(U$3-1)") (class "Default")
      (node (ref "C1") (pin "P$1") (pinfunction "P$1_P$1") (pintype "passive"))
      (node (ref "R1") (pin "P$1") (pinfunction "P$1_P$1") (pintype "passive"))
      (node (ref "U$3") (pin "P$1") (pinfunction "1_P$1") (pintype "passive"))
    )
    (net (code "50") (name "Net-(U1-LX)") (class "Default")
      (node (ref "L1") (pin "2") (pinfunction "2_2") (pintype "passive"))
      (node (ref "U1") (pin "8") (pinfunction "LX_8") (pintype "passive"))
    )
    (net (code "51") (name "Net-(U1-VCC)") (class "Default")
      (node (ref "C3") (pin "P$1") (pinfunction "P$1_P$1") (pintype "passive"))
      (node (ref "U1") (pin "3") (pinfunction "VCC_3") (pintype "power_in"))
    )
    (net (code "52") (name "Net-(U2-PA1)") (class "Default")
      (node (ref "R26") (pin "P$1") (pinfunction "P$1_P$1") (pintype "passive"))
      (node (ref "U2") (pin "9") (pinfunction "PA1_9") (pintype "bidirectional"))
    )
    (net (code "53") (name "Net-(U2-PA3)") (class "Default")
      (node (ref "C23") (pin "P$1") (pinfunction "P$1_P$1") (pintype "passive"))
      (node (ref "U2") (pin "11") (pinfunction "PA3_11") (pintype "bidirectional"))
    )
    (net (code "54") (name "Net-(U5-FIL+)") (class "Default")
      (node (ref "C17") (pin "P$2") (pinfunction "P$2_P$2") (pintype "passive"))
      (node (ref "U5") (pin "8") (pinfunction "FIL+_8") (pintype "passive"))
    )
    (net (code "55") (name "Net-(U5-FIL-)") (class "Default")
      (node (ref "C17") (pin "P$1") (pinfunction "P$1_P$1") (pintype "passive"))
      (node (ref "U5") (pin "1") (pinfunction "FIL-_1") (pintype "passive"))
    )
    (net (code "56") (name "Net-(U5-VBIAS)") (class "Default")
      (node (ref "R24") (pin "P$2") (pinfunction "P$2_P$2") (pintype "passive"))
      (node (ref "U5") (pin "6") (pinfunction "VBIAS_6") (pintype "output"))
    )
    (net (code "57") (name "VCC") (class "Default")
      (node (ref "C10") (pin "P$1") (pinfunction "P$1_P$1") (pintype "passive"))
      (node (ref "C11") (pin "P$1") (pinfunction "P$1_P$1") (pintype "passive"))
      (node (ref "C16") (pin "P$1") (pinfunction "P$1_P$1") (pintype "passive"))
      (node (ref "C21") (pin "P$1") (pinfunction "P$1_P$1") (pintype "passive"))
      (node (ref "C4") (pin "P$1") (pinfunction "P$1_P$1") (pintype "passive"))
      (node (ref "C6") (pin "P$1") (pinfunction "P$1_P$1") (pintype "passive"))
      (node (ref "C7") (pin "P$1") (pinfunction "P$1_P$1") (pintype "passive"))
      (node (ref "C8") (pin "P$1") (pinfunction "P$1_P$1") (pintype "passive"))
      (node (ref "C9") (pin "P$1") (pinfunction "P$1_P$1") (pintype "passive"))
      (node (ref "DB_3") (pin "P$1") (pinfunction "P$1_P$1") (pintype "bidirectional"))
      (node (ref "J1") (pin "6") (pinfunction "6_6") (pintype "passive"))
      (node (ref "J3") (pin "1") (pinfunction "1_1") (pintype "passive"))
      (node (ref "L1") (pin "1") (pinfunction "1_1") (pintype "passive"))
      (node (ref "R10") (pin "P$2") (pinfunction "P$2_P$2") (pintype "passive"))
      (node (ref "R21") (pin "P$2") (pinfunction "P$2_P$2") (pintype "passive"))
      (node (ref "R23") (pin "P$2") (pinfunction "P$2_P$2") (pintype "passive"))
      (node (ref "R9") (pin "P$2") (pinfunction "P$2_P$2") (pintype "passive"))
      (node (ref "U1") (pin "4") (pinfunction "FB/VOUT_4") (pintype "bidirectional"))
      (node (ref "U2") (pin "1") (pinfunction "VBAT_1") (pintype "bidirectional"))
      (node (ref "U2") (pin "20") (pinfunction "VREF+_20") (pintype "bidirectional"))
      (node (ref "U2") (pin "21") (pinfunction "VDDA_21") (pintype "bidirectional"))
      (node (ref "U2") (pin "23") (pinfunction "VDD_1_23") (pintype "bidirectional"))
      (node (ref "U2") (pin "35") (pinfunction "VDD_2_35") (pintype "bidirectional"))
      (node (ref "U2") (pin "48") (pinfunction "VDD_3_48") (pintype "bidirectional"))
      (node (ref "U4") (pin "3") (pinfunction "VCC_3") (pintype "power_in"))
      (node (ref "U6") (pin "4") (pinfunction "VCC_4") (pintype "power_in"))
    )
    (net (code "58") (name "unconnected-(J1-Pad1)") (class "Default")
      (node (ref "J1") (pin "1") (pinfunction "1_1") (pintype "passive"))
    )
    (net (code "59") (name "unconnected-(U$1-1-PadP$1)") (class "Default")
      (node (ref "U$1") (pin "P$1") (pinfunction "1_P$1") (pintype "passive"))
    )
    (net (code "60") (name "unconnected-(U$2-1-PadP$1)") (class "Default")
      (node (ref "U$2") (pin "P$1") (pinfunction "1_P$1") (pintype "passive"))
    )
    (net (code "61") (name "unconnected-(U$4-1-PadP$1)") (class "Default")
      (node (ref "U$4") (pin "P$1") (pinfunction "1_P$1") (pintype "passive"))
    )
    (net (code "62") (name "unconnected-(U1-MODE-Pad5)") (class "Default")
      (node (ref "U1") (pin "5") (pinfunction "MODE_5") (pintype "input"))
    )
    (net (code "63") (name "unconnected-(U1-~{RESET}-Pad6)") (class "Default")
      (node (ref "U1") (pin "6") (pinfunction "~{RESET}_6") (pintype "output"))
    )
    (net (code "64") (name "unconnected-(U2-PA6-Pad14)") (class "Default")
      (node (ref "U2") (pin "14") (pinfunction "PA6_14") (pintype "bidirectional"))
    )
    (net (code "65") (name "unconnected-(U2-PA9-Pad31)") (class "Default")
      (node (ref "U2") (pin "31") (pinfunction "PA9_31") (pintype "bidirectional"))
    )
    (net (code "66") (name "unconnected-(U2-PB2-Pad19)") (class "Default")
      (node (ref "U2") (pin "19") (pinfunction "PB2_19") (pintype "bidirectional"))
    )
    (net (code "67") (name "unconnected-(U2-PB4-Pad42)") (class "Default")
      (node (ref "U2") (pin "42") (pinfunction "PB4_42") (pintype "bidirectional"))
    )
    (net (code "68") (name "unconnected-(U2-PB5-Pad43)") (class "Default")
      (node (ref "U2") (pin "43") (pinfunction "PB5_43") (pintype "bidirectional"))
    )
    (net (code "69") (name "unconnected-(U2-PB6-Pad44)") (class "Default")
      (node (ref "U2") (pin "44") (pinfunction "PB6_44") (pintype "bidirectional"))
    )
    (net (code "70") (name "unconnected-(U2-PB7-Pad45)") (class "Default")
      (node (ref "U2") (pin "45") (pinfunction "PB7_45") (pintype "bidirectional"))
    )
    (net (code "71") (name "unconnected-(U2-PB8-BOOT0-Pad46)") (class "Default")
      (node (ref "U2") (pin "46") (pinfunction "PB8-BOOT0_46") (pintype "bidirectional"))
    )
    (net (code "72") (name "unconnected-(U2-PB10-Pad22)") (class "Default")
      (node (ref "U2") (pin "22") (pinfunction "PB10_22") (pintype "bidirectional"))
    )
    (net (code "73") (name "unconnected-(U2-PC6-Pad29)") (class "Default")
      (node (ref "U2") (pin "29") (pinfunction "PC6_29") (pintype "bidirectional"))
    )
    (net (code "74") (name "unconnected-(U2-PC13-Pad2)") (class "Default")
      (node (ref "U2") (pin "2") (pinfunction "PC13_2") (pintype "bidirectional"))
    )
    (net (code "75") (name "unconnected-(U2-PC15-OSC32_OUT-Pad4)") (class "Default")
      (node (ref "U2") (pin "4") (pinfunction "PC15-OSC32_OUT_4") (pintype "bidirectional"))
    )
    (net (code "76") (name "unconnected-(U2-PF0-OSC_IN-Pad5)") (class "Default")
      (node (ref "U2") (pin "5") (pinfunction "PF0-OSC_IN_5") (pintype "bidirectional"))
    )
    (net (code "77") (name "unconnected-(U2-PF1-OSC_OUT-Pad6)") (class "Default")
      (node (ref "U2") (pin "6") (pinfunction "PF1-OSC_OUT_6") (pintype "bidirectional"))
    )
    (net (code "78") (name "unconnected-(U5-DNC-Pad3)") (class "Default")
      (node (ref "U5") (pin "3") (pinfunction "DNC_3") (pintype "no_connect"))
    )
    (net (code "79") (name "unconnected-(U6-NC-Pad2)") (class "Default")
      (node (ref "U6") (pin "2") (pinfunction "NC_2") (pintype "no_connect"))
    )
  )
)
